# A03_CURRENT_ADC.net
KiCad netlist of a schematic drawn in Altium Designer
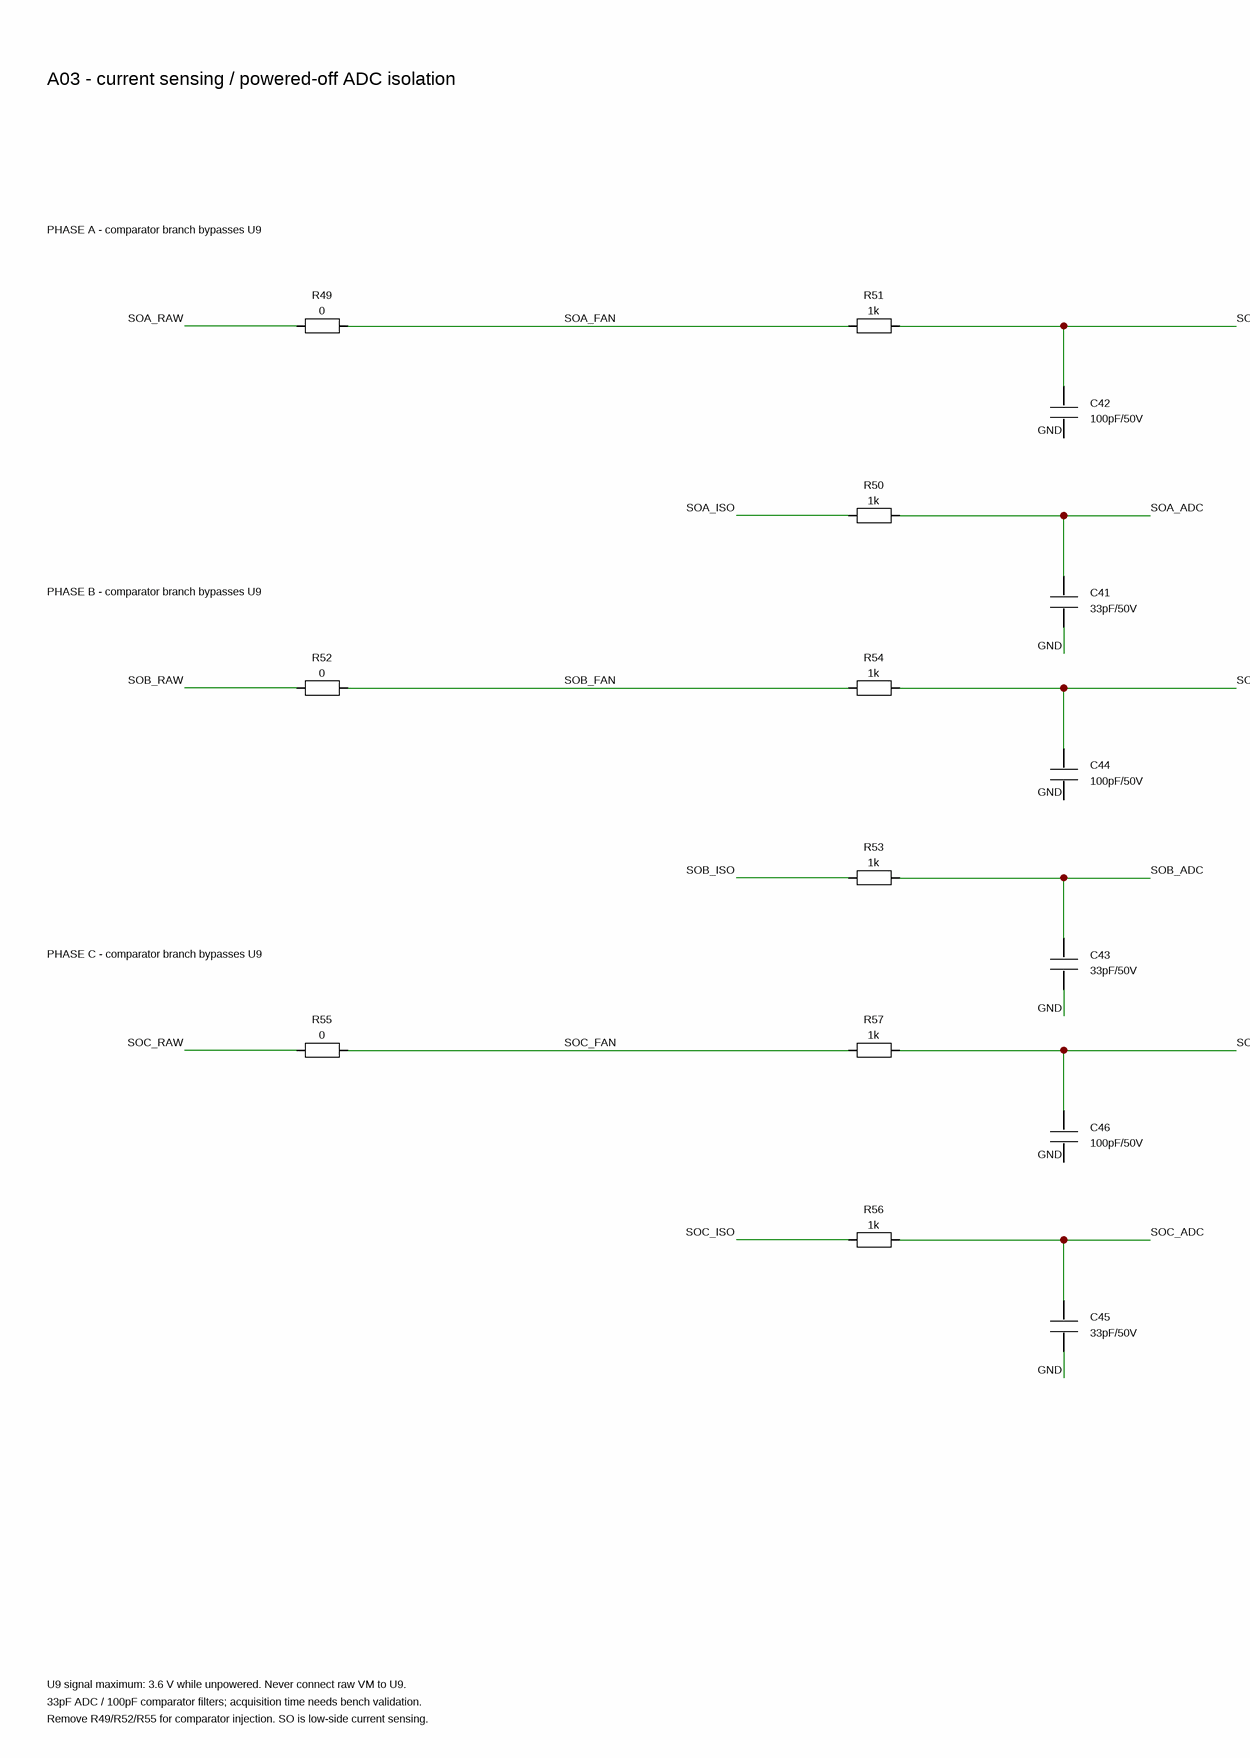
[diagram p0: A03_CURRENT_ADC.SchDoc, left]
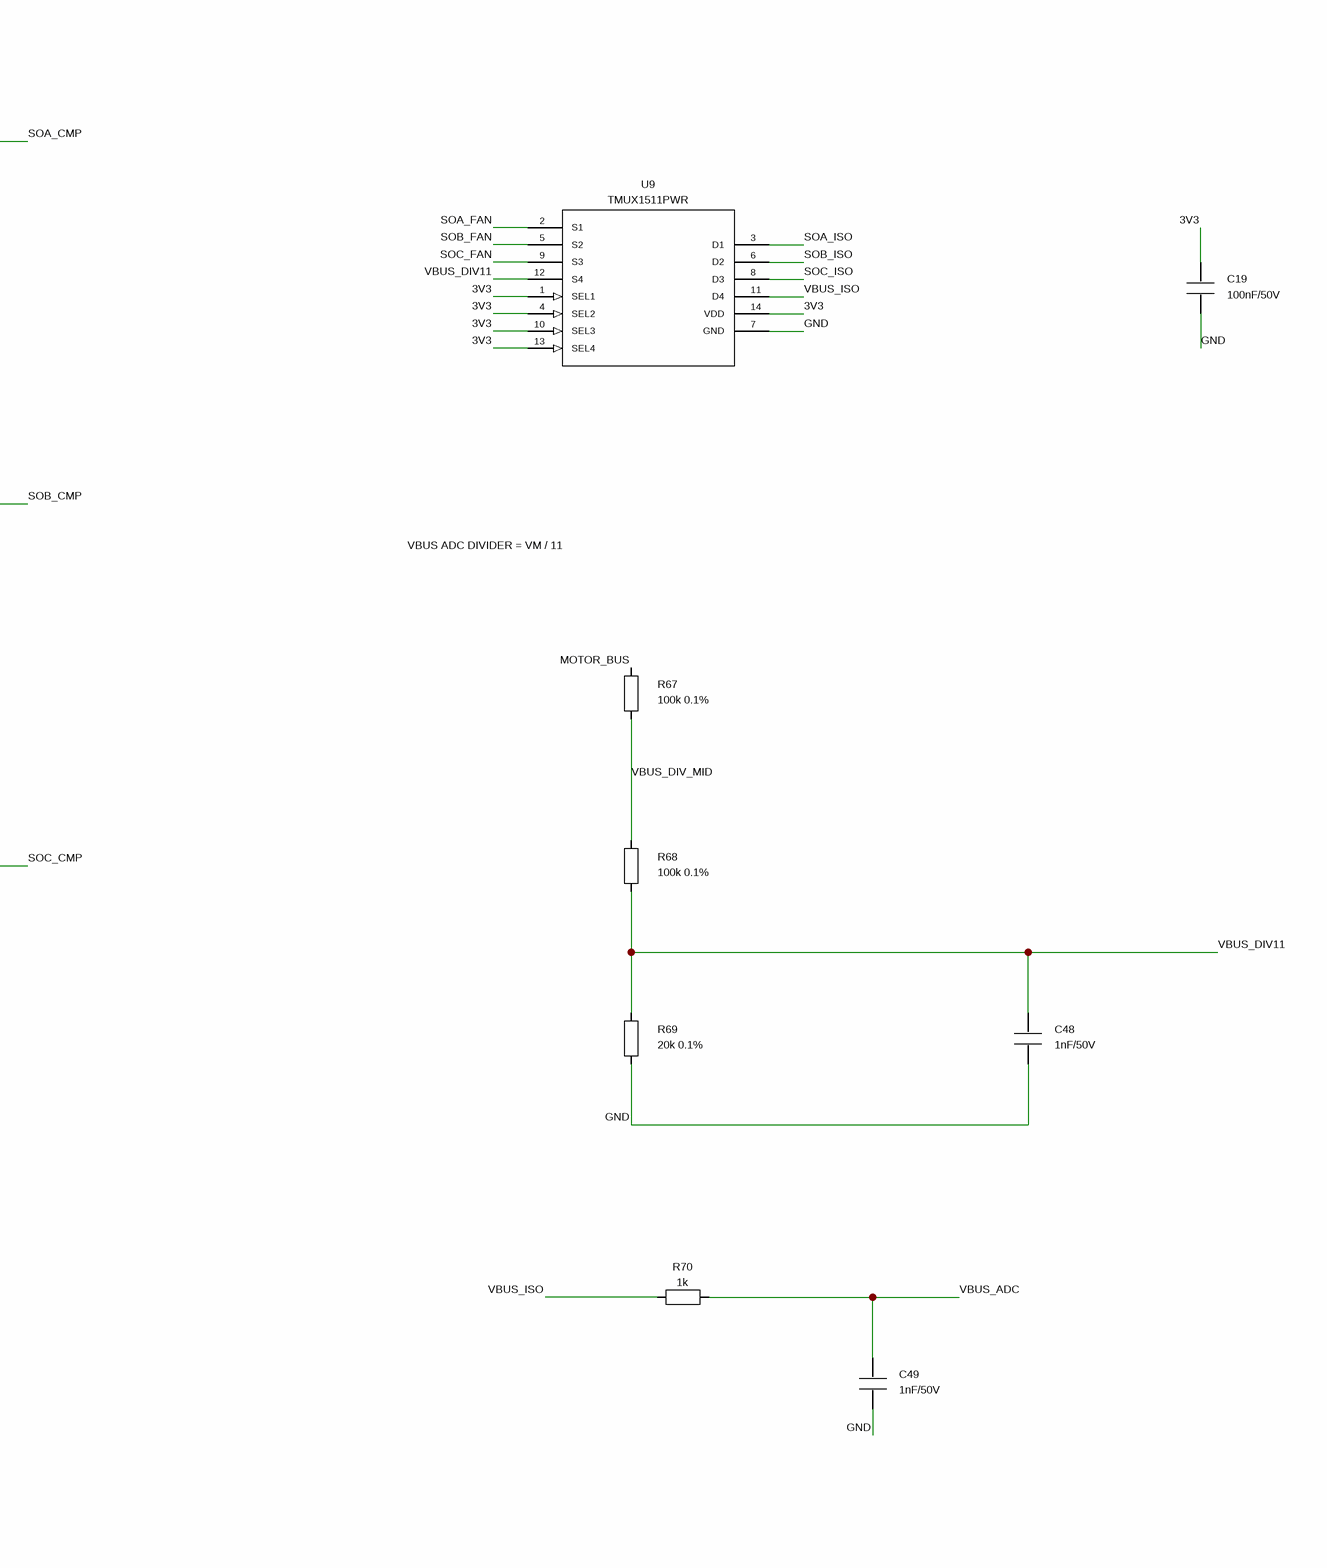
[diagram p1: A03_CURRENT_ADC.SchDoc, right]

(export (version "E")
  (design (tool "Eeschema 10.0.6"))
  (components
    (comp (ref "C19")
      (value "100nF/50V")
      (footprint "User_STM32F407_Ctrl:C0603_M")
      (description "电容")
      (fields (field (name "MPN") "CL10B104KB8NNNC"))
      (libsource (lib "altium-import") (part "root_0_C_"))
    )
    (comp (ref "C41")
      (value "33pF/50V")
      (footprint "User_STM32F407_Ctrl:C0603_M")
      (description "电容")
      (fields (field (name "MPN") "CC0603JRNPO9BN330"))
      (libsource (lib "altium-import") (part "root_0_C_"))
    )
    (comp (ref "C42")
      (value "100pF/50V")
      (footprint "User_STM32F407_Ctrl:C0603_M")
      (description "电容")
      (fields (field (name "MPN") "CC0603JRNPO9BN101"))
      (libsource (lib "altium-import") (part "root_0_C_"))
    )
    (comp (ref "C43")
      (value "33pF/50V")
      (footprint "User_STM32F407_Ctrl:C0603_M")
      (description "电容")
      (fields (field (name "MPN") "CC0603JRNPO9BN330"))
      (libsource (lib "altium-import") (part "root_0_C_"))
    )
    (comp (ref "C44")
      (value "100pF/50V")
      (footprint "User_STM32F407_Ctrl:C0603_M")
      (description "电容")
      (fields (field (name "MPN") "CC0603JRNPO9BN101"))
      (libsource (lib "altium-import") (part "root_0_C_"))
    )
    (comp (ref "C45")
      (value "33pF/50V")
      (footprint "User_STM32F407_Ctrl:C0603_M")
      (description "电容")
      (fields (field (name "MPN") "CC0603JRNPO9BN330"))
      (libsource (lib "altium-import") (part "root_0_C_"))
    )
    (comp (ref "C46")
      (value "100pF/50V")
      (footprint "User_STM32F407_Ctrl:C0603_M")
      (description "电容")
      (fields (field (name "MPN") "CC0603JRNPO9BN101"))
      (libsource (lib "altium-import") (part "root_0_C_"))
    )
    (comp (ref "C48")
      (value "1nF/50V")
      (footprint "User_STM32F407_Ctrl:C0603_M")
      (description "电容")
      (fields (field (name "MPN") "CL10B102KB8NNNC"))
      (libsource (lib "altium-import") (part "root_0_C_"))
    )
    (comp (ref "C49")
      (value "1nF/50V")
      (footprint "User_STM32F407_Ctrl:C0603_M")
      (description "电容")
      (fields (field (name "MPN") "CL10B102KB8NNNC"))
      (libsource (lib "altium-import") (part "root_0_C_"))
    )
    (comp (ref "R49")
      (value "0")
      (footprint "User_STM32F407_Ctrl:R0603_M")
      (description "电阻")
      (fields (field (name "MPN") "通用0Ω跳线 0.1 W"))
      (libsource (lib "altium-import") (part "root_1_R_"))
    )
    (comp (ref "R50")
      (value "1k")
      (footprint "User_STM32F407_Ctrl:R0603_M")
      (description "电阻")
      (fields (field (name "MPN") "通用厚膜 1k 1% 0.1 W"))
      (libsource (lib "altium-import") (part "root_1_R_"))
    )
    (comp (ref "R51")
      (value "1k")
      (footprint "User_STM32F407_Ctrl:R0603_M")
      (description "电阻")
      (fields (field (name "MPN") "通用厚膜 1k 1% 0.1 W"))
      (libsource (lib "altium-import") (part "root_1_R_"))
    )
    (comp (ref "R52")
      (value "0")
      (footprint "User_STM32F407_Ctrl:R0603_M")
      (description "电阻")
      (fields (field (name "MPN") "通用0Ω跳线 0.1 W"))
      (libsource (lib "altium-import") (part "root_1_R_"))
    )
    (comp (ref "R53")
      (value "1k")
      (footprint "User_STM32F407_Ctrl:R0603_M")
      (description "电阻")
      (fields (field (name "MPN") "通用厚膜 1k 1% 0.1 W"))
      (libsource (lib "altium-import") (part "root_1_R_"))
    )
    (comp (ref "R54")
      (value "1k")
      (footprint "User_STM32F407_Ctrl:R0603_M")
      (description "电阻")
      (fields (field (name "MPN") "通用厚膜 1k 1% 0.1 W"))
      (libsource (lib "altium-import") (part "root_1_R_"))
    )
    (comp (ref "R55")
      (value "0")
      (footprint "User_STM32F407_Ctrl:R0603_M")
      (description "电阻")
      (fields (field (name "MPN") "通用0Ω跳线 0.1 W"))
      (libsource (lib "altium-import") (part "root_1_R_"))
    )
    (comp (ref "R56")
      (value "1k")
      (footprint "User_STM32F407_Ctrl:R0603_M")
      (description "电阻")
      (fields (field (name "MPN") "通用厚膜 1k 1% 0.1 W"))
      (libsource (lib "altium-import") (part "root_1_R_"))
    )
    (comp (ref "R57")
      (value "1k")
      (footprint "User_STM32F407_Ctrl:R0603_M")
      (description "电阻")
      (fields (field (name "MPN") "通用厚膜 1k 1% 0.1 W"))
      (libsource (lib "altium-import") (part "root_1_R_"))
    )
    (comp (ref "R67")
      (value "100k 0.1%")
      (footprint "User_STM32F407_Ctrl:R0603_M")
      (description "电阻")
      (fields (field (name "MPN") "RT0603BRD07100KL"))
      (libsource (lib "altium-import") (part "root_0_R_"))
    )
    (comp (ref "R68")
      (value "100k 0.1%")
      (footprint "User_STM32F407_Ctrl:R0603_M")
      (description "电阻")
      (fields (field (name "MPN") "RT0603BRD07100KL"))
      (libsource (lib "altium-import") (part "root_0_R_"))
    )
    (comp (ref "R69")
      (value "20k 0.1%")
      (footprint "User_STM32F407_Ctrl:R0603_M")
      (description "电阻")
      (fields (field (name "MPN") "TNPW060320K0BEEA"))
      (libsource (lib "altium-import") (part "root_0_R_"))
    )
    (comp (ref "R70")
      (value "1k")
      (footprint "User_STM32F407_Ctrl:R0603_M")
      (description "电阻")
      (fields (field (name "MPN") "通用厚膜 1k 1% 0.1 W"))
      (libsource (lib "altium-import") (part "root_1_R_"))
    )
    (comp (ref "U9")
      (value "TMUX1511PWR")
      (footprint "User_SamacSys:SOP65P640X120-14N")
      (description "四路采样断电隔离")
      (libsource (lib "altium-import") (part "root_0_TMUX1511PWR_"))
    )
  )
  (nets
    (net (code "1") (name "/3V3") (class "Default")
      (node (ref "C19") (pin "1") (pintype "passive"))
      (node (ref "U9") (pin "1") (pinfunction "SEL1_1") (pintype "input"))
      (node (ref "U9") (pin "10") (pinfunction "SEL3_10") (pintype "input"))
      (node (ref "U9") (pin "13") (pinfunction "SEL4_13") (pintype "input"))
      (node (ref "U9") (pin "14") (pinfunction "VDD_14") (pintype "power_in"))
      (node (ref "U9") (pin "4") (pinfunction "SEL2_4") (pintype "input"))
    )
    (net (code "2") (name "/GND") (class "Default")
      (node (ref "C19") (pin "2") (pintype "passive"))
      (node (ref "C41") (pin "2") (pintype "passive"))
      (node (ref "C42") (pin "2") (pintype "passive"))
      (node (ref "C43") (pin "2") (pintype "passive"))
      (node (ref "C44") (pin "2") (pintype "passive"))
      (node (ref "C45") (pin "2") (pintype "passive"))
      (node (ref "C46") (pin "2") (pintype "passive"))
      (node (ref "C48") (pin "2") (pintype "passive"))
      (node (ref "C49") (pin "2") (pintype "passive"))
      (node (ref "R69") (pin "2") (pintype "passive"))
      (node (ref "U9") (pin "7") (pinfunction "GND_7") (pintype "power_in"))
    )
    (net (code "3") (name "/MOTOR_BUS") (class "Default") (node (ref "R67") (pin "1") (pintype "passive")))
    (net (code "4") (name "/SOA_ADC") (class "Default")
      (node (ref "C41") (pin "1") (pintype "passive"))
      (node (ref "R50") (pin "2") (pintype "passive"))
    )
    (net (code "5") (name "/SOA_CMP") (class "Default")
      (node (ref "C42") (pin "1") (pintype "passive"))
      (node (ref "R51") (pin "2") (pintype "passive"))
    )
    (net (code "6") (name "/SOA_FAN") (class "Default")
      (node (ref "R49") (pin "2") (pintype "passive"))
      (node (ref "R51") (pin "1") (pintype "passive"))
      (node (ref "U9") (pin "2") (pinfunction "S1_2") (pintype "passive"))
    )
    (net (code "7") (name "/SOA_ISO") (class "Default")
      (node (ref "R50") (pin "1") (pintype "passive"))
      (node (ref "U9") (pin "3") (pinfunction "D1_3") (pintype "passive"))
    )
    (net (code "8") (name "/SOA_RAW") (class "Default") (node (ref "R49") (pin "1") (pintype "passive")))
    (net (code "9") (name "/SOB_ADC") (class "Default")
      (node (ref "C43") (pin "1") (pintype "passive"))
      (node (ref "R53") (pin "2") (pintype "passive"))
    )
    (net (code "10") (name "/SOB_CMP") (class "Default")
      (node (ref "C44") (pin "1") (pintype "passive"))
      (node (ref "R54") (pin "2") (pintype "passive"))
    )
    (net (code "11") (name "/SOB_FAN") (class "Default")
      (node (ref "R52") (pin "2") (pintype "passive"))
      (node (ref "R54") (pin "1") (pintype "passive"))
      (node (ref "U9") (pin "5") (pinfunction "S2_5") (pintype "passive"))
    )
    (net (code "12") (name "/SOB_ISO") (class "Default")
      (node (ref "R53") (pin "1") (pintype "passive"))
      (node (ref "U9") (pin "6") (pinfunction "D2_6") (pintype "passive"))
    )
    (net (code "13") (name "/SOB_RAW") (class "Default") (node (ref "R52") (pin "1") (pintype "passive")))
    (net (code "14") (name "/SOC_ADC") (class "Default")
      (node (ref "C45") (pin "1") (pintype "passive"))
      (node (ref "R56") (pin "2") (pintype "passive"))
    )
    (net (code "15") (name "/SOC_CMP") (class "Default")
      (node (ref "C46") (pin "1") (pintype "passive"))
      (node (ref "R57") (pin "2") (pintype "passive"))
    )
    (net (code "16") (name "/SOC_FAN") (class "Default")
      (node (ref "R55") (pin "2") (pintype "passive"))
      (node (ref "R57") (pin "1") (pintype "passive"))
      (node (ref "U9") (pin "9") (pinfunction "S3_9") (pintype "passive"))
    )
    (net (code "17") (name "/SOC_ISO") (class "Default")
      (node (ref "R56") (pin "1") (pintype "passive"))
      (node (ref "U9") (pin "8") (pinfunction "D3_8") (pintype "passive"))
    )
    (net (code "18") (name "/SOC_RAW") (class "Default") (node (ref "R55") (pin "1") (pintype "passive")))
    (net (code "19") (name "/VBUS_ADC") (class "Default")
      (node (ref "C49") (pin "1") (pintype "passive"))
      (node (ref "R70") (pin "2") (pintype "passive"))
    )
    (net (code "20") (name "/VBUS_DIV11") (class "Default")
      (node (ref "C48") (pin "1") (pintype "passive"))
      (node (ref "R68") (pin "2") (pintype "passive"))
      (node (ref "R69") (pin "1") (pintype "passive"))
      (node (ref "U9") (pin "12") (pinfunction "S4_12") (pintype "passive"))
    )
    (net (code "21") (name "/VBUS_DIV_MID") (class "Default")
      (node (ref "R67") (pin "2") (pintype "passive"))
      (node (ref "R68") (pin "1") (pintype "passive"))
    )
    (net (code "22") (name "/VBUS_ISO") (class "Default")
      (node (ref "R70") (pin "1") (pintype "passive"))
      (node (ref "U9") (pin "11") (pinfunction "D4_11") (pintype "passive"))
    )
  )
)
